# SolderingStation_Control.net
KiCad netlist of a schematic drawn in Altium Designer
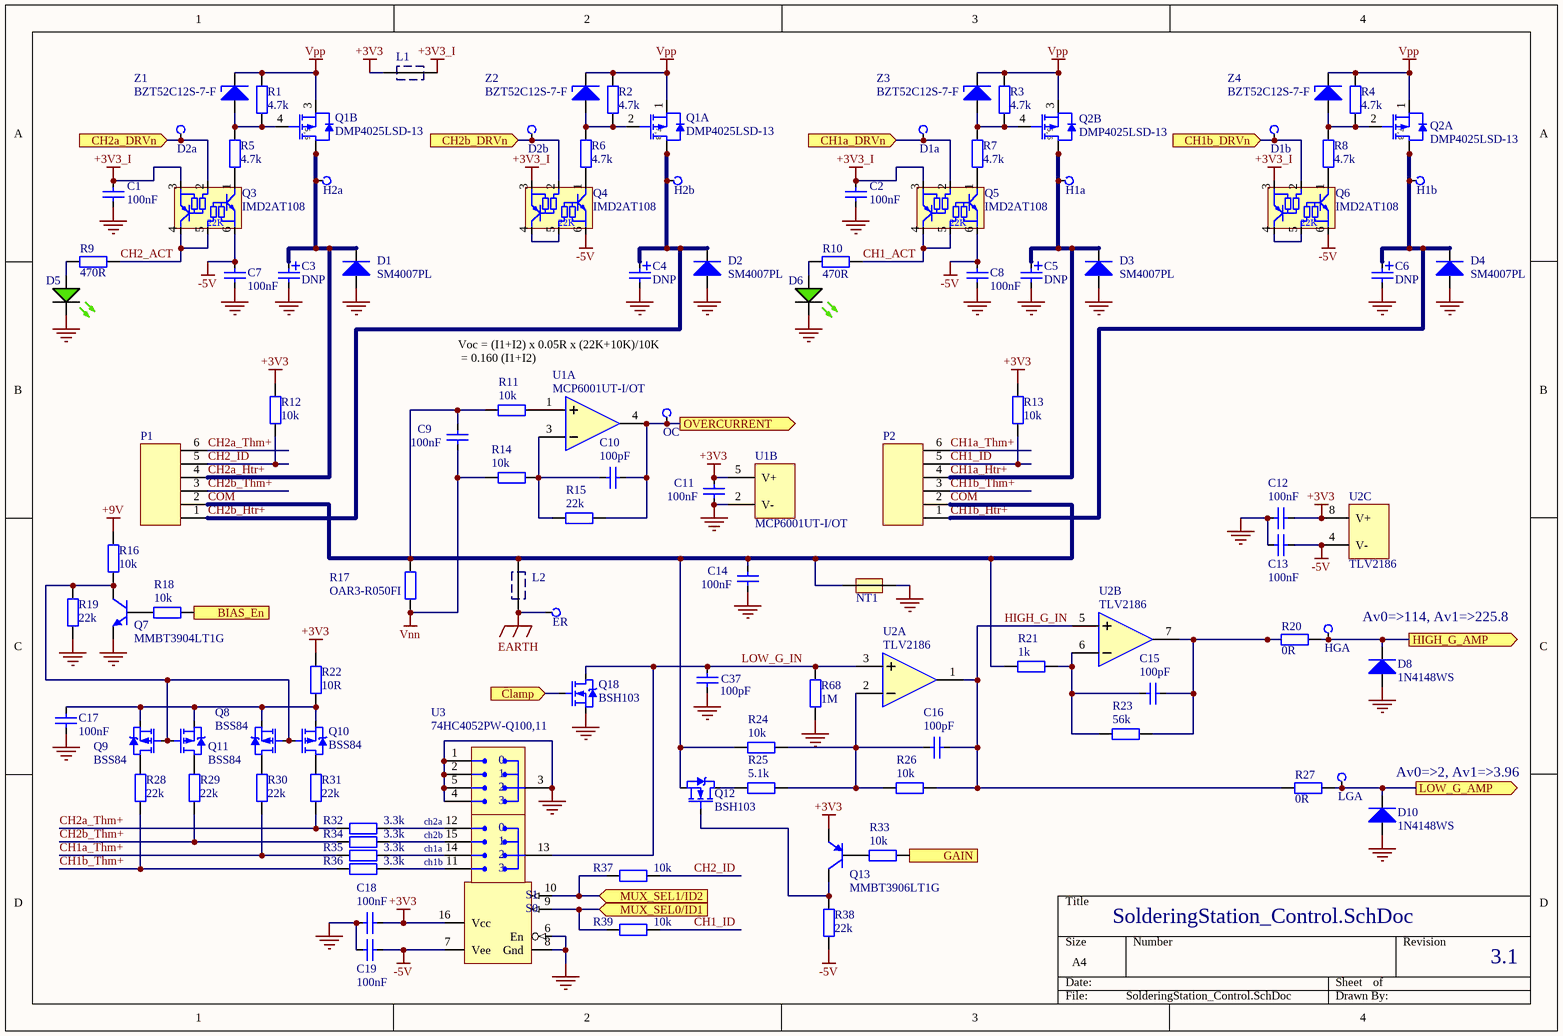
[diagram p0: SolderingStation_Control.SchDoc]

(export (version "E")
  (design (tool "Eeschema 10.0.6"))
  (components
    (comp (ref "C1")
      (value "100nF")
      (footprint "CCNP1608-0603_N")
      (description "Capacitor non-polar SMT 0603")
      (fields
        (field (name "MANUFACTURER") "Generic Components")
        (field (name "PUBLISHER") "Altium Hobart Technology Centre")
      )
      (libsource (lib "MyLibrary") (part "Cap_CCNP_0603_100nF"))
    )
    (comp (ref "C2")
      (value "100nF")
      (footprint "CCNP1608-0603_N")
      (description "Capacitor non-polar SMT 0603")
      (fields
        (field (name "MANUFACTURER") "Generic Components")
        (field (name "PUBLISHER") "Altium Hobart Technology Centre")
      )
      (libsource (lib "MyLibrary") (part "Cap_CCNP_0603_100nF"))
    )
    (comp (ref "C3")
      (value "DNP")
      (footprint "CC2012-0805")
      (description "Capacitor SMT 0805")
      (fields
        (field (name "MANUFACTURER") "Generic Components")
        (field (name "PUBLISHER") "Altium Hobart Technology Centre")
      )
      (libsource (lib "MyLibrary") (part "Cap_CC_0805"))
    )
    (comp (ref "C4")
      (value "DNP")
      (footprint "CC2012-0805")
      (description "Capacitor SMT 0805")
      (fields
        (field (name "MANUFACTURER") "Generic Components")
        (field (name "PUBLISHER") "Altium Hobart Technology Centre")
      )
      (libsource (lib "MyLibrary") (part "Cap_CC_0805"))
    )
    (comp (ref "C5")
      (value "DNP")
      (footprint "CC2012-0805")
      (description "Capacitor SMT 0805")
      (fields
        (field (name "MANUFACTURER") "Generic Components")
        (field (name "PUBLISHER") "Altium Hobart Technology Centre")
      )
      (libsource (lib "MyLibrary") (part "Cap_CC_0805"))
    )
    (comp (ref "C6")
      (value "DNP")
      (footprint "CC2012-0805")
      (description "Capacitor SMT 0805")
      (fields
        (field (name "MANUFACTURER") "Generic Components")
        (field (name "PUBLISHER") "Altium Hobart Technology Centre")
      )
      (libsource (lib "MyLibrary") (part "Cap_CC_0805"))
    )
    (comp (ref "C7")
      (value "100nF")
      (footprint "CCNP1608-0603_N")
      (description "Capacitor non-polar SMT 0603")
      (fields
        (field (name "MANUFACTURER") "Generic Components")
        (field (name "PUBLISHER") "Altium Hobart Technology Centre")
      )
      (libsource (lib "MyLibrary") (part "Cap_CCNP_0603_100nF"))
    )
    (comp (ref "C8")
      (value "100nF")
      (footprint "CCNP1608-0603_N")
      (description "Capacitor non-polar SMT 0603")
      (fields
        (field (name "MANUFACTURER") "Generic Components")
        (field (name "PUBLISHER") "Altium Hobart Technology Centre")
      )
      (libsource (lib "MyLibrary") (part "Cap_CCNP_0603_100nF"))
    )
    (comp (ref "C9")
      (value "100nF")
      (footprint "CCNP1608-0603_N")
      (description "Capacitor non-polar SMT 0603")
      (fields
        (field (name "MANUFACTURER") "Generic Components")
        (field (name "PUBLISHER") "Altium Hobart Technology Centre")
      )
      (libsource (lib "MyLibrary") (part "Cap_CCNP_0603_100nF"))
    )
    (comp (ref "C10")
      (value "100pF")
      (footprint "CCNP1608-0603_N")
      (description "Capacitor non-polar SMT 0603")
      (fields
        (field (name "MANUFACTURER") "Generic Components")
        (field (name "PUBLISHER") "Altium Hobart Technology Centre")
      )
      (libsource (lib "MyLibrary") (part "Cap_CCNP_0603_100pF"))
    )
    (comp (ref "C11")
      (value "100nF")
      (footprint "CCNP1608-0603_N")
      (description "Capacitor non-polar SMT 0603")
      (fields
        (field (name "MANUFACTURER") "Generic Components")
        (field (name "PUBLISHER") "Altium Hobart Technology Centre")
      )
      (libsource (lib "MyLibrary") (part "Cap_CCNP_0603_100nF"))
    )
    (comp (ref "C12")
      (value "100nF")
      (footprint "CCNP1608-0603_N")
      (description "Capacitor non-polar SMT 0603")
      (fields
        (field (name "MANUFACTURER") "Generic Components")
        (field (name "PUBLISHER") "Altium Hobart Technology Centre")
      )
      (libsource (lib "MyLibrary") (part "Cap_CCNP_0603_100nF"))
    )
    (comp (ref "C13")
      (value "100nF")
      (footprint "CCNP1608-0603_N")
      (description "Capacitor non-polar SMT 0603")
      (fields
        (field (name "MANUFACTURER") "Generic Components")
        (field (name "PUBLISHER") "Altium Hobart Technology Centre")
      )
      (libsource (lib "MyLibrary") (part "Cap_CCNP_0603_100nF"))
    )
    (comp (ref "C14")
      (value "100nF")
      (footprint "CCNP1608-0603_N")
      (description "Capacitor non-polar SMT 0603")
      (fields
        (field (name "MANUFACTURER") "Generic Components")
        (field (name "PUBLISHER") "Altium Hobart Technology Centre")
      )
      (libsource (lib "MyLibrary") (part "Cap_CCNP_0603_100nF"))
    )
    (comp (ref "C15")
      (value "100pF")
      (footprint "CCNP1608-0603_N")
      (description "Capacitor non-polar SMT 0603")
      (fields
        (field (name "MANUFACTURER") "Generic Components")
        (field (name "PUBLISHER") "Altium Hobart Technology Centre")
      )
      (libsource (lib "MyLibrary") (part "Cap_CCNP_0603_100pF"))
    )
    (comp (ref "C16")
      (value "100pF")
      (footprint "CCNP1608-0603_N")
      (description "Capacitor non-polar SMT 0603")
      (fields
        (field (name "MANUFACTURER") "Generic Components")
        (field (name "PUBLISHER") "Altium Hobart Technology Centre")
      )
      (libsource (lib "MyLibrary") (part "Cap_CCNP_0603_100pF"))
    )
    (comp (ref "C17")
      (value "100nF")
      (footprint "CCNP1608-0603_N")
      (description "Capacitor non-polar SMT 0603")
      (fields
        (field (name "MANUFACTURER") "Generic Components")
        (field (name "PUBLISHER") "Altium Hobart Technology Centre")
      )
      (libsource (lib "MyLibrary") (part "Cap_CCNP_0603_100nF"))
    )
    (comp (ref "C18")
      (value "100nF")
      (footprint "CCNP1608-0603_N")
      (description "Capacitor non-polar SMT 0603")
      (fields
        (field (name "MANUFACTURER") "Generic Components")
        (field (name "PUBLISHER") "Altium Hobart Technology Centre")
      )
      (libsource (lib "MyLibrary") (part "Cap_CCNP_0603_100nF"))
    )
    (comp (ref "C19")
      (value "100nF")
      (footprint "CCNP1608-0603_N")
      (description "Capacitor non-polar SMT 0603")
      (fields
        (field (name "MANUFACTURER") "Generic Components")
        (field (name "PUBLISHER") "Altium Hobart Technology Centre")
      )
      (libsource (lib "MyLibrary") (part "Cap_CCNP_0603_100nF"))
    )
    (comp (ref "C37")
      (value "100pF")
      (footprint "CCNP1608-0603_N")
      (description "Capacitor non-polar SMT 0603")
      (fields
        (field (name "MANUFACTURER") "Generic Components")
        (field (name "PUBLISHER") "Altium Hobart Technology Centre")
      )
      (libsource (lib "MyLibrary") (part "Cap_CCNP_0603_100pF"))
    )
    (comp (ref "D1")
      (value "SM4007PL")
      (footprint "SOD-123FL")
      (description "Diodes - General Purpose, 1kV 1A 1.1V 1A SOD-123FL")
      (libsource (lib "MyLibrary") (part "SM4007PL"))
    )
    (comp (ref "D1a")
      (value "Drive1")
      (footprint "PCBPIN - 0.9mm")
      (description "Test Point")
      (libsource (lib "") (part "TP_1"))
    )
    (comp (ref "D1b")
      (value "Drive2")
      (footprint "PCBPIN - 0.9mm")
      (description "Test Point")
      (libsource (lib "") (part "TP_1"))
    )
    (comp (ref "D2")
      (value "SM4007PL")
      (footprint "SOD-123FL")
      (description "Diodes - General Purpose, 1kV 1A 1.1V 1A SOD-123FL")
      (libsource (lib "MyLibrary") (part "SM4007PL"))
    )
    (comp (ref "D2a")
      (value "Drive2")
      (footprint "PCBPIN - 0.9mm")
      (description "Test Point")
      (libsource (lib "") (part "TP_1"))
    )
    (comp (ref "D2b")
      (value "Drive2")
      (footprint "PCBPIN - 0.9mm")
      (description "Test Point")
      (libsource (lib "") (part "TP_1"))
    )
    (comp (ref "D3")
      (value "SM4007PL")
      (footprint "SOD-123FL")
      (description "Diodes - General Purpose, 1kV 1A 1.1V 1A SOD-123FL")
      (libsource (lib "MyLibrary") (part "SM4007PL"))
    )
    (comp (ref "D4")
      (value "SM4007PL")
      (footprint "SOD-123FL")
      (description "Diodes - General Purpose, 1kV 1A 1.1V 1A SOD-123FL")
      (libsource (lib "MyLibrary") (part "SM4007PL"))
    )
    (comp (ref "D5")
      (value "LED")
      (footprint "LED3MM-GREEN - 10mm Proud")
      (description "3mm Green LED")
      (fields (field (name "MANUFACTURER") "Generic Components") (field (name "PUBLISHER") "Altium Limited"))
      (libsource (lib "MySchLib") (part "LED_3MM_GREEN"))
    )
    (comp (ref "D6")
      (value "LED")
      (footprint "LED3MM-GREEN - 10mm Proud")
      (description "3mm Green LED")
      (fields (field (name "MANUFACTURER") "Generic Components") (field (name "PUBLISHER") "Altium Limited"))
      (libsource (lib "MySchLib") (part "LED_3MM_GREEN"))
    )
    (comp (ref "D8")
      (value "1N4148WS")
      (footprint "SOD-323")
      (description "Switching Diode 100V 150mA 1.25V@150mA 4ns SOD-323")
      (libsource (lib "MyLibrary") (part "1N4148WS"))
    )
    (comp (ref "D10")
      (value "1N4148WS")
      (footprint "SOD-323")
      (description "Switching Diode 100V 150mA 1.25V@150mA 4ns SOD-323")
      (libsource (lib "MyLibrary") (part "1N4148WS"))
    )
    (comp (ref "ER")
      (value "Gnd")
      (footprint "PCBPIN - 0.9mm")
      (description "Test Point")
      (libsource (lib "MySchLib") (part "TP"))
    )
    (comp (ref "H1a")
      (value "Heater1")
      (footprint "PCBPIN - 0.9mm")
      (description "Test Point")
      (libsource (lib "MySchLib") (part "TP"))
    )
    (comp (ref "H1b")
      (value "Heater2")
      (footprint "PCBPIN - 0.9mm")
      (description "Test Point")
      (libsource (lib "MySchLib") (part "TP"))
    )
    (comp (ref "H2a")
      (value "Heater2")
      (footprint "PCBPIN - 0.9mm")
      (description "Test Point")
      (libsource (lib "MySchLib") (part "TP"))
    )
    (comp (ref "H2b")
      (value "Heater2")
      (footprint "PCBPIN - 0.9mm")
      (description "Test Point")
      (libsource (lib "MySchLib") (part "TP"))
    )
    (comp (ref "HGA")
      (value "TC1")
      (footprint "PCBPIN - 0.9mm")
      (description "Test Point")
      (libsource (lib "") (part "TP_1"))
    )
    (comp (ref "L1")
      (value "Ferrite Bead")
      (footprint "FB2012-0805")
      (description "Ferrite Bead SMT 0805, TDK MPZ2012S102AT, 0.15OHM, 1.5A")
      (libsource (lib "MySchLib") (part "Ferrite Bead 0805"))
    )
    (comp (ref "L2")
      (value "Ferrite Bead")
      (footprint "FB2012-0805")
      (description "Ferrite Bead SMT 0805, TDK MPZ2012S102AT, 0.15OHM, 1.5A")
      (libsource (lib "MySchLib") (part "Ferrite Bead 0805"))
    )
    (comp (ref "LGA")
      (value "NTC1")
      (footprint "PCBPIN - 0.9mm")
      (description "Test Point")
      (libsource (lib "") (part "TP_1"))
    )
    (comp (ref "NT1")
      (value "NetTieVia")
      (footprint "NetTieVia")
      (libsource (lib "MyLibrary") (part "NetTieVia"))
    )
    (comp (ref "OC")
      (value "Overcurrent")
      (footprint "PCBPIN - 0.9mm")
      (description "Test Point")
      (libsource (lib "") (part "TP_1"))
    )
    (comp (ref "P1")
      (value "MOLEX-43045-0612")
      (footprint "MOLEX-43045-0612")
      (description "Wire-To-Board Connector, With Polarizing Peg, 3 mm, 6 Contacts, Header, Micro-Fit 3.0 43045 Series")
      (libsource (lib "MySchLib") (part "MOLEX-43045-0612"))
    )
    (comp (ref "P2")
      (value "MOLEX-43045-0612")
      (footprint "MOLEX-43045-0612")
      (description "Wire-To-Board Connector, With Polarizing Peg, 3 mm, 6 Contacts, Header, Micro-Fit 3.0 43045 Series")
      (libsource (lib "MySchLib") (part "MOLEX-43045-0612"))
    )
    (comp (ref "Q1")
      (value "DMP4025LSD-13")
      (footprint "SO-8_M")
      (description "P-Channel dual MOSFET, 40 V, 7.6 A, 0.018 ohm, SOIC, Surface Mount")
      (libsource (lib "MyLibrary") (part "DMP4025LSD-13"))
    )
    (comp (ref "Q2")
      (value "DMP4025LSD-13")
      (footprint "SO-8_M")
      (description "P-Channel dual MOSFET, 40 V, 7.6 A, 0.018 ohm, SOIC, Surface Mount")
      (libsource (lib "MyLibrary") (part "DMP4025LSD-13"))
    )
    (comp (ref "Q3")
      (value "IMD2AT108")
      (footprint "SOT457_N - MIRROR")
      (description "Pre-Biased NPN and PNP pair, 50 V, 100 mA, 22 kohm, 22 kohm")
      (libsource (lib "MySchLib") (part "IMD2AT108"))
    )
    (comp (ref "Q4")
      (value "IMD2AT108")
      (footprint "SOT457_N - MIRROR")
      (description "Pre-Biased NPN and PNP pair, 50 V, 100 mA, 22 kohm, 22 kohm")
      (libsource (lib "MySchLib") (part "IMD2AT108"))
    )
    (comp (ref "Q5")
      (value "IMD2AT108")
      (footprint "SOT457_N - MIRROR")
      (description "Pre-Biased NPN and PNP pair, 50 V, 100 mA, 22 kohm, 22 kohm")
      (libsource (lib "MySchLib") (part "IMD2AT108"))
    )
    (comp (ref "Q6")
      (value "IMD2AT108")
      (footprint "SOT457_N - MIRROR")
      (description "Pre-Biased NPN and PNP pair, 50 V, 100 mA, 22 kohm, 22 kohm")
      (libsource (lib "MySchLib") (part "IMD2AT108"))
    )
    (comp (ref "Q7")
      (value "MMBT3904LT1G")
      (footprint "SOT23_N")
      (description "General Purpose Transistor, NPN Silicon, 3-Pin SOT-23, Pb-Free, Tape and Reel")
      (fields (field (name "MANUFACTURER") "On Semiconductor"))
      (libsource (lib "MyLibrary") (part "MMBT3904LT1G"))
    )
    (comp (ref "Q8")
      (value "BSS84")
      (footprint "SOT23_M")
      (description "P-Channel Enhancement Mode FET -0.13 A, -50 V,  RDS(ON) = 10R at VGS = -5 V")
      (libsource (lib "MySchLib") (part "BSS84"))
    )
    (comp (ref "Q9")
      (value "BSS84")
      (footprint "SOT23_M")
      (description "P-Channel Enhancement Mode FET -0.13 A, -50 V,  RDS(ON) = 10R at VGS = -5 V")
      (libsource (lib "MySchLib") (part "BSS84"))
    )
    (comp (ref "Q10")
      (value "BSS84")
      (footprint "SOT23_M")
      (description "P-Channel Enhancement Mode FET -0.13 A, -50 V,  RDS(ON) = 10R at VGS = -5 V")
      (libsource (lib "MySchLib") (part "BSS84"))
    )
    (comp (ref "Q11")
      (value "BSS84")
      (footprint "SOT23_M")
      (description "P-Channel Enhancement Mode FET -0.13 A, -50 V,  RDS(ON) = 10R at VGS = -5 V")
      (libsource (lib "MySchLib") (part "BSS84"))
    )
    (comp (ref "Q12")
      (value "BSH103")
      (footprint "SOT23_N")
      (description "N-channel enhancement mode FET, , 30 V, 850 mA, 0.4 ohm, SOT23")
      (libsource (lib "MyLibrary") (part "BSH103"))
    )
    (comp (ref "Q13")
      (value "MMBT3906LT1G")
      (footprint "SOT23_N")
      (description "General Purpose Transistor, PNP Silicon, 3-Pin SOT-23, Pb-Free, Tape and Reel")
      (fields (field (name "MANUFACTURER") "On Semiconductor"))
      (libsource (lib "MyLibrary") (part "MMBT3906LT1G"))
    )
    (comp (ref "Q18")
      (value "BSH103")
      (footprint "SOT23_N")
      (description "N-channel enhancement mode FET, , 30 V, 850 mA, 0.4 ohm, SOT23")
      (libsource (lib "MyLibrary") (part "BSH103"))
    )
    (comp (ref "R1")
      (value "4.7k")
      (footprint "CR1608-0603_N")
      (description "Resistor SMT 0603")
      (fields
        (field (name "MANUFACTURER") "Generic Components")
        (field (name "PUBLISHER") "Altium Hobart Technology Centre")
      )
      (libsource (lib "MyLibrary") (part "Res_CR0603_4k7"))
    )
    (comp (ref "R2")
      (value "4.7k")
      (footprint "CR1608-0603_N")
      (description "Resistor SMT 0603")
      (fields
        (field (name "MANUFACTURER") "Generic Components")
        (field (name "PUBLISHER") "Altium Hobart Technology Centre")
      )
      (libsource (lib "MyLibrary") (part "Res_CR0603_4k7"))
    )
    (comp (ref "R3")
      (value "4.7k")
      (footprint "CR1608-0603_N")
      (description "Resistor SMT 0603")
      (fields
        (field (name "MANUFACTURER") "Generic Components")
        (field (name "PUBLISHER") "Altium Hobart Technology Centre")
      )
      (libsource (lib "MyLibrary") (part "Res_CR0603_4k7"))
    )
    (comp (ref "R4")
      (value "4.7k")
      (footprint "CR1608-0603_N")
      (description "Resistor SMT 0603")
      (fields
        (field (name "MANUFACTURER") "Generic Components")
        (field (name "PUBLISHER") "Altium Hobart Technology Centre")
      )
      (libsource (lib "MyLibrary") (part "Res_CR0603_4k7"))
    )
    (comp (ref "R5")
      (value "4.7k")
      (footprint "CR1608-0603_N")
      (description "Resistor SMT 0603")
      (fields
        (field (name "MANUFACTURER") "Generic Components")
        (field (name "PUBLISHER") "Altium Hobart Technology Centre")
      )
      (libsource (lib "MyLibrary") (part "Res_CR0603_4k7"))
    )
    (comp (ref "R6")
      (value "4.7k")
      (footprint "CR1608-0603_N")
      (description "Resistor SMT 0603")
      (fields
        (field (name "MANUFACTURER") "Generic Components")
        (field (name "PUBLISHER") "Altium Hobart Technology Centre")
      )
      (libsource (lib "MyLibrary") (part "Res_CR0603_4k7"))
    )
    (comp (ref "R7")
      (value "4.7k")
      (footprint "CR1608-0603_N")
      (description "Resistor SMT 0603")
      (fields
        (field (name "MANUFACTURER") "Generic Components")
        (field (name "PUBLISHER") "Altium Hobart Technology Centre")
      )
      (libsource (lib "MyLibrary") (part "Res_CR0603_4k7"))
    )
    (comp (ref "R8")
      (value "4.7k")
      (footprint "CR1608-0603_N")
      (description "Resistor SMT 0603")
      (fields
        (field (name "MANUFACTURER") "Generic Components")
        (field (name "PUBLISHER") "Altium Hobart Technology Centre")
      )
      (libsource (lib "MyLibrary") (part "Res_CR0603_4k7"))
    )
    (comp (ref "R9")
      (value "470R")
      (footprint "CR1608-0603_N")
      (description "Resistor SMT 0603")
      (fields
        (field (name "MANUFACTURER") "Generic Components")
        (field (name "PUBLISHER") "Altium Hobart Technology Centre")
      )
      (libsource (lib "MyLibrary") (part "Res_CR0603_470R"))
    )
    (comp (ref "R10")
      (value "470R")
      (footprint "CR1608-0603_N")
      (description "Resistor SMT 0603")
      (fields
        (field (name "MANUFACTURER") "Generic Components")
        (field (name "PUBLISHER") "Altium Hobart Technology Centre")
      )
      (libsource (lib "MyLibrary") (part "Res_CR0603_470R"))
    )
    (comp (ref "R11")
      (value "10k")
      (footprint "CR1608-0603_N")
      (description "Resistor SMT 0603")
      (fields
        (field (name "MANUFACTURER") "Generic Components")
        (field (name "PUBLISHER") "Altium Hobart Technology Centre")
      )
      (libsource (lib "") (part "Res_CR0603_10k_1"))
    )
    (comp (ref "R12")
      (value "10k")
      (footprint "CR1608-0603_N")
      (description "Resistor SMT 0603")
      (fields
        (field (name "MANUFACTURER") "Generic Components")
        (field (name "PUBLISHER") "Altium Hobart Technology Centre")
      )
      (libsource (lib "MyLibrary") (part "Res_CR0603_10k"))
    )
    (comp (ref "R13")
      (value "10k")
      (footprint "CR1608-0603_N")
      (description "Resistor SMT 0603")
      (fields
        (field (name "MANUFACTURER") "Generic Components")
        (field (name "PUBLISHER") "Altium Hobart Technology Centre")
      )
      (libsource (lib "MyLibrary") (part "Res_CR0603_10k"))
    )
    (comp (ref "R14")
      (value "10k")
      (footprint "CR1608-0603_N")
      (description "Resistor SMT 0603")
      (fields
        (field (name "MANUFACTURER") "Generic Components")
        (field (name "PUBLISHER") "Altium Hobart Technology Centre")
      )
      (libsource (lib "") (part "Res_CR0603_10k_1"))
    )
    (comp (ref "R15")
      (value "22k")
      (footprint "CR1608-0603_N")
      (description "Resistor SMT 0603")
      (fields
        (field (name "MANUFACTURER") "Generic Components")
        (field (name "PUBLISHER") "Altium Hobart Technology Centre")
      )
      (libsource (lib "") (part "Res_CR0603_22k_1"))
    )
    (comp (ref "R16")
      (value "10k")
      (footprint "CR1608-0603_N")
      (description "Resistor SMT 0603")
      (fields
        (field (name "MANUFACTURER") "Generic Components")
        (field (name "PUBLISHER") "Altium Hobart Technology Centre")
      )
      (libsource (lib "") (part "Res_CR0603_10k_3"))
    )
    (comp (ref "R17")
      (value "OAR3-R050FI")
      (footprint "OAR3-R050FI")
      (description "Current Sense Resistor, 0.05 ohm, OAR Series, 3 W, Metal Strip, Radial Leaded, 1%")
      (libsource (lib "MySchLib") (part "OAR3-R050FI"))
    )
    (comp (ref "R18")
      (value "10k")
      (footprint "CR1608-0603_N")
      (description "Resistor SMT 0603")
      (fields
        (field (name "MANUFACTURER") "Generic Components")
        (field (name "PUBLISHER") "Altium Hobart Technology Centre")
      )
      (libsource (lib "") (part "Res_CR0603_10k_2"))
    )
    (comp (ref "R19")
      (value "22k")
      (footprint "CR1608-0603_N")
      (description "Resistor SMT 0603")
      (fields
        (field (name "MANUFACTURER") "Generic Components")
        (field (name "PUBLISHER") "Altium Hobart Technology Centre")
      )
      (libsource (lib "MyLibrary") (part "Res_CR0603_22k"))
    )
    (comp (ref "R20")
      (value "0R")
      (footprint "CR1608-0603_N")
      (description "Resistor SMT 0603")
      (fields
        (field (name "MANUFACTURER") "Generic Components")
        (field (name "PUBLISHER") "Altium Hobart Technology Centre")
      )
      (libsource (lib "MyLibrary") (part "Res_CR0603_0R"))
    )
    (comp (ref "R21")
      (value "1k")
      (footprint "CR1608-0603_N")
      (description "Resistor SMT 0603")
      (fields
        (field (name "MANUFACTURER") "Generic Components")
        (field (name "PUBLISHER") "Altium Hobart Technology Centre")
      )
      (libsource (lib "MyLibrary") (part "Res_CR0603_1k"))
    )
    (comp (ref "R22")
      (value "10R")
      (footprint "CR1608-0603_N")
      (description "Resistor SMT 0603")
      (fields
        (field (name "MANUFACTURER") "Generic Components")
        (field (name "PUBLISHER") "Altium Hobart Technology Centre")
      )
      (libsource (lib "MyLibrary") (part "Res_CR0603_10R"))
    )
    (comp (ref "R23")
      (value "56k")
      (footprint "CR1608-0603_N")
      (description "Resistor SMT 0603")
      (fields
        (field (name "MANUFACTURER") "Generic Components")
        (field (name "PUBLISHER") "Altium Hobart Technology Centre")
      )
      (libsource (lib "MyLibrary") (part "Res_CR0603_56k"))
    )
    (comp (ref "R24")
      (value "10k")
      (footprint "CR1608-0603_N")
      (description "Resistor SMT 0603")
      (fields
        (field (name "MANUFACTURER") "Generic Components")
        (field (name "PUBLISHER") "Altium Hobart Technology Centre")
      )
      (libsource (lib "") (part "Res_CR0603_10k_2"))
    )
    (comp (ref "R25")
      (value "5.1k")
      (footprint "CR1608-0603_N")
      (description "Resistor SMT 0603")
      (fields
        (field (name "MANUFACTURER") "Generic Components")
        (field (name "PUBLISHER") "Altium Hobart Technology Centre")
      )
      (libsource (lib "MyLibrary") (part "Res_CR0603_5k1"))
    )
    (comp (ref "R26")
      (value "10k")
      (footprint "CR1608-0603_N")
      (description "Resistor SMT 0603")
      (fields
        (field (name "MANUFACTURER") "Generic Components")
        (field (name "PUBLISHER") "Altium Hobart Technology Centre")
      )
      (libsource (lib "") (part "Res_CR0603_10k_2"))
    )
    (comp (ref "R27")
      (value "0R")
      (footprint "CR1608-0603_N")
      (description "Resistor SMT 0603")
      (fields
        (field (name "MANUFACTURER") "Generic Components")
        (field (name "PUBLISHER") "Altium Hobart Technology Centre")
      )
      (libsource (lib "MyLibrary") (part "Res_CR0603_0R"))
    )
    (comp (ref "R28")
      (value "22k")
      (footprint "CR1608-0603_N")
      (description "Resistor SMT 0603")
      (fields
        (field (name "MANUFACTURER") "Generic Components")
        (field (name "PUBLISHER") "Altium Hobart Technology Centre")
      )
      (libsource (lib "") (part "Res_CR0603_22k_1"))
    )
    (comp (ref "R29")
      (value "22k")
      (footprint "CR1608-0603_N")
      (description "Resistor SMT 0603")
      (fields
        (field (name "MANUFACTURER") "Generic Components")
        (field (name "PUBLISHER") "Altium Hobart Technology Centre")
      )
      (libsource (lib "") (part "Res_CR0603_22k_1"))
    )
    (comp (ref "R30")
      (value "22k")
      (footprint "CR1608-0603_N")
      (description "Resistor SMT 0603")
      (fields
        (field (name "MANUFACTURER") "Generic Components")
        (field (name "PUBLISHER") "Altium Hobart Technology Centre")
      )
      (libsource (lib "MyLibrary") (part "Res_CR0603_22k"))
    )
    (comp (ref "R31")
      (value "22k")
      (footprint "CR1608-0603_N")
      (description "Resistor SMT 0603")
      (fields
        (field (name "MANUFACTURER") "Generic Components")
        (field (name "PUBLISHER") "Altium Hobart Technology Centre")
      )
      (libsource (lib "MyLibrary") (part "Res_CR0603_22k"))
    )
    (comp (ref "R32")
      (value "3.3k")
      (footprint "CR1608-0603_N")
      (description "Resistor SMT 0603")
      (fields
        (field (name "MANUFACTURER") "Generic Components")
        (field (name "PUBLISHER") "Altium Hobart Technology Centre")
      )
      (libsource (lib "MyLibrary") (part "Res_CR0603_3k3"))
    )
    (comp (ref "R33")
      (value "10k")
      (footprint "CR1608-0603_N")
      (description "Resistor SMT 0603")
      (fields
        (field (name "MANUFACTURER") "Generic Components")
        (field (name "PUBLISHER") "Altium Hobart Technology Centre")
      )
      (libsource (lib "") (part "Res_CR0603_10k_2"))
    )
    (comp (ref "R34")
      (value "3.3k")
      (footprint "CR1608-0603_N")
      (description "Resistor SMT 0603")
      (fields
        (field (name "MANUFACTURER") "Generic Components")
        (field (name "PUBLISHER") "Altium Hobart Technology Centre")
      )
      (libsource (lib "MyLibrary") (part "Res_CR0603_3k3"))
    )
    (comp (ref "R35")
      (value "3.3k")
      (footprint "CR1608-0603_N")
      (description "Resistor SMT 0603")
      (fields
        (field (name "MANUFACTURER") "Generic Components")
        (field (name "PUBLISHER") "Altium Hobart Technology Centre")
      )
      (libsource (lib "MyLibrary") (part "Res_CR0603_3k3"))
    )
    (comp (ref "R36")
      (value "3.3k")
      (footprint "CR1608-0603_N")
      (description "Resistor SMT 0603")
      (fields
        (field (name "MANUFACTURER") "Generic Components")
        (field (name "PUBLISHER") "Altium Hobart Technology Centre")
      )
      (libsource (lib "MyLibrary") (part "Res_CR0603_3k3"))
    )
    (comp (ref "R37")
      (value "10k")
      (footprint "CR1608-0603_N")
      (description "Resistor SMT 0603")
      (fields
        (field (name "MANUFACTURER") "Generic Components")
        (field (name "PUBLISHER") "Altium Hobart Technology Centre")
      )
      (libsource (lib "") (part "Res_CR0603_10k_3"))
    )
    (comp (ref "R38")
      (value "22k")
      (footprint "CR1608-0603_N")
      (description "Resistor SMT 0603")
      (fields
        (field (name "MANUFACTURER") "Generic Components")
        (field (name "PUBLISHER") "Altium Hobart Technology Centre")
      )
      (libsource (lib "MyLibrary") (part "Res_CR0603_22k"))
    )
    (comp (ref "R39")
      (value "10k")
      (footprint "CR1608-0603_N")
      (description "Resistor SMT 0603")
      (fields
        (field (name "MANUFACTURER") "Generic Components")
        (field (name "PUBLISHER") "Altium Hobart Technology Centre")
      )
      (libsource (lib "") (part "Res_CR0603_10k_3"))
    )
    (comp (ref "R68")
      (value "1M")
      (footprint "CR1608-0603_N")
      (description "Resistor SMT 0603")
      (fields
        (field (name "MANUFACTURER") "Generic Components")
        (field (name "PUBLISHER") "Altium Hobart Technology Centre")
      )
      (libsource (lib "MyLibrary") (part "Res_CR0603_1M"))
    )
    (comp (ref "U1")
      (value "MCP6001UT-I/OT")
      (footprint "SOT23-5_M")
      (description "Op-Amp, Single supply R-R in/out")
      (libsource (lib "") (part "MCP6001UT-I/OT_1"))
    )
    (comp (ref "U2")
      (value "TLV2186")
      (footprint "SOIC127P600-8M")
      (description "Dual Precision,Rail-to-Rail Input and Output, 4.5-24V, Zero-Drift OperationalAmplifier")
      (libsource (lib "MySchLib") (part "TLV2186"))
    )
    (comp (ref "U3")
      (value "74HC4052PW-Q100,11")
      (footprint "TSSOP16_M")
      (description "Analog Multiplexer / Demultiplexer, 4:1, 2 Circuits, 225 ohm, 2V to 10V, TSSOP-16")
      (libsource (lib "MySchLib") (part "74HC4052PW-Q100,11"))
    )
    (comp (ref "Z1")
      (value "BZT52C12S-7-F")
      (footprint "SOD-323")
      (description "Surface Mount Zener Diode, 12-13 V, -65 to 150 degC, SOD-123")
      (libsource (lib "MySchLib") (part "BZT52C12S-7-F"))
    )
    (comp (ref "Z2")
      (value "BZT52C12S-7-F")
      (footprint "SOD-323")
      (description "Surface Mount Zener Diode, 12-13 V, -65 to 150 degC, SOD-123")
      (libsource (lib "MySchLib") (part "BZT52C12S-7-F"))
    )
    (comp (ref "Z3")
      (value "BZT52C12S-7-F")
      (footprint "SOD-323")
      (description "Surface Mount Zener Diode, 12-13 V, -65 to 150 degC, SOD-123")
      (libsource (lib "MySchLib") (part "BZT52C12S-7-F"))
    )
    (comp (ref "Z4")
      (value "BZT52C12S-7-F")
      (footprint "SOD-323")
      (description "Surface Mount Zener Diode, 12-13 V, -65 to 150 degC, SOD-123")
      (libsource (lib "MySchLib") (part "BZT52C12S-7-F"))
    )
  )
  (nets
    (net (code "1") (name "+3V3") (class "Default")
      (node (ref "C11") (pin "1") (pinfunction "1_1") (pintype "passive"))
      (node (ref "C12") (pin "1") (pinfunction "1_1") (pintype "passive"))
      (node (ref "C18") (pin "1") (pinfunction "1_1") (pintype "passive"))
      (node (ref "L1") (pin "1") (pinfunction "1_1") (pintype "passive"))
      (node (ref "Q13") (pin "2") (pinfunction "E_2") (pintype "passive"))
      (node (ref "R12") (pin "2") (pinfunction "2_2") (pintype "passive"))
      (node (ref "R13") (pin "2") (pinfunction "2_2") (pintype "passive"))
      (node (ref "R22") (pin "1") (pinfunction "1_1") (pintype "passive"))
      (node (ref "U1") (pin "5") (pinfunction "V+_5") (pintype "power_in"))
      (node (ref "U2") (pin "8") (pinfunction "V+_8") (pintype "power_in"))
      (node (ref "U3") (pin "16") (pinfunction "Vcc_16") (pintype "power_in"))
    )
    (net (code "2") (name "+3V3_I") (class "Default")
      (node (ref "C1") (pin "1") (pinfunction "1_1") (pintype "passive"))
      (node (ref "C2") (pin "1") (pinfunction "1_1") (pintype "passive"))
      (node (ref "L1") (pin "2") (pinfunction "2_2") (pintype "passive"))
      (node (ref "Q3") (pin "3") (pinfunction "E2_3") (pintype "passive"))
      (node (ref "Q4") (pin "3") (pinfunction "E2_3") (pintype "passive"))
      (node (ref "Q5") (pin "3") (pinfunction "E2_3") (pintype "passive"))
      (node (ref "Q6") (pin "3") (pinfunction "E2_3") (pintype "passive"))
    )
    (net (code "3") (name "+9V") (class "Default")
      (node (ref "R16") (pin "1") (pinfunction "1_1") (pintype "passive"))
    )
    (net (code "4") (name "-5V") (class "Default")
      (node (ref "C13") (pin "1") (pinfunction "1_1") (pintype "passive"))
      (node (ref "C19") (pin "1") (pinfunction "1_1") (pintype "passive"))
      (node (ref "C7") (pin "1") (pinfunction "1_1") (pintype "passive"))
      (node (ref "C8") (pin "1") (pinfunction "1_1") (pintype "passive"))
      (node (ref "Q3") (pin "6") (pinfunction "E1_6") (pintype "passive"))
      (node (ref "Q4") (pin "6") (pinfunction "E1_6") (pintype "passive"))
      (node (ref "Q5") (pin "6") (pinfunction "E1_6") (pintype "passive"))
      (node (ref "Q6") (pin "6") (pinfunction "E1_6") (pintype "passive"))
      (node (ref "R38") (pin "1") (pinfunction "1_1") (pintype "passive"))
      (node (ref "U2") (pin "4") (pinfunction "V-_4") (pintype "power_in"))
      (node (ref "U3") (pin "7") (pinfunction "Vee_7") (pintype "power_in"))
    )
    (net (code "5") (name "/BIAS_En") (class "Default")
      (node (ref "R18") (pin "2") (pinfunction "2_2") (pintype "passive"))
    )
    (net (code "6") (name "/CH1_ACT") (class "Default")
      (node (ref "Q5") (pin "4") (pinfunction "C2_4") (pintype "passive"))
      (node (ref "Q5") (pin "5") (pinfunction "B1_5") (pintype "passive"))
      (node (ref "R10") (pin "2") (pinfunction "2_2") (pintype "passive"))
    )
    (net (code "7") (name "/CH1_ID") (class "Default")
      (node (ref "P2") (pin "5") (pinfunction "5_5") (pintype "passive"))
      (node (ref "R13") (pin "1") (pinfunction "1_1") (pintype "passive"))
      (node (ref "R39") (pin "1") (pinfunction "1_1") (pintype "passive"))
    )
    (net (code "8") (name "/CH1a_DRVn") (class "Default")
      (node (ref "D1a") (pin "1") (pinfunction "TP_1") (pintype "passive"))
      (node (ref "Q5") (pin "2") (pinfunction "B2_2") (pintype "passive"))
    )
    (net (code "9") (name "/CH1a_Htr+") (class "Default")
      (node (ref "C5") (pin "1") (pinfunction "1_1") (pintype "passive"))
      (node (ref "D3") (pin "K") (pinfunction "K_K") (pintype "passive"))
      (node (ref "H1a") (pin "1") (pinfunction "TP_1") (pintype "passive"))
      (node (ref "P2") (pin "4") (pinfunction "4_4") (pintype "passive"))
      (node (ref "Q2") (pin "5") (pinfunction "D2_5") (pintype "passive"))
      (node (ref "Q2") (pin "6") (pinfunction "D2_6") (pintype "passive"))
    )
    (net (code "10") (name "/CH1a_Thm+") (class "Default")
      (node (ref "P2") (pin "6") (pinfunction "6_6") (pintype "passive"))
      (node (ref "R30") (pin "1") (pinfunction "1_1") (pintype "passive"))
      (node (ref "R35") (pin "2") (pinfunction "2_2") (pintype "passive"))
    )
    (net (code "11") (name "/CH1b_DRVn") (class "Default")
      (node (ref "D1b") (pin "1") (pinfunction "TP_1") (pintype "passive"))
      (node (ref "Q6") (pin "2") (pinfunction "B2_2") (pintype "passive"))
    )
    (net (code "12") (name "/CH1b_Htr+") (class "Default")
      (node (ref "C6") (pin "1") (pinfunction "1_1") (pintype "passive"))
      (node (ref "D4") (pin "K") (pinfunction "K_K") (pintype "passive"))
      (node (ref "H1b") (pin "1") (pinfunction "TP_1") (pintype "passive"))
      (node (ref "P2") (pin "1") (pinfunction "1_1") (pintype "passive"))
      (node (ref "Q2") (pin "7") (pinfunction "D1_7") (pintype "passive"))
      (node (ref "Q2") (pin "8") (pinfunction "D1_8") (pintype "passive"))
    )
    (net (code "13") (name "/CH1b_Thm+") (class "Default")
      (node (ref "P2") (pin "3") (pinfunction "3_3") (pintype "passive"))
      (node (ref "R28") (pin "1") (pinfunction "1_1") (pintype "passive"))
      (node (ref "R36") (pin "2") (pinfunction "2_2") (pintype "passive"))
    )
    (net (code "14") (name "/CH2_ACT") (class "Default")
      (node (ref "Q3") (pin "4") (pinfunction "C2_4") (pintype "passive"))
      (node (ref "Q3") (pin "5") (pinfunction "B1_5") (pintype "passive"))
      (node (ref "R9") (pin "2") (pinfunction "2_2") (pintype "passive"))
    )
    (net (code "15") (name "/CH2_ID") (class "Default")
      (node (ref "P1") (pin "5") (pinfunction "5_5") (pintype "passive"))
      (node (ref "R12") (pin "1") (pinfunction "1_1") (pintype "passive"))
      (node (ref "R37") (pin "1") (pinfunction "1_1") (pintype "passive"))
    )
    (net (code "16") (name "/CH2a_DRVn") (class "Default")
      (node (ref "D2a") (pin "1") (pinfunction "TP_1") (pintype "passive"))
      (node (ref "Q3") (pin "2") (pinfunction "B2_2") (pintype "passive"))
    )
    (net (code "17") (name "/CH2a_Htr+") (class "Default")
      (node (ref "C3") (pin "1") (pinfunction "1_1") (pintype "passive"))
      (node (ref "D1") (pin "K") (pinfunction "K_K") (pintype "passive"))
      (node (ref "H2a") (pin "1") (pinfunction "TP_1") (pintype "passive"))
      (node (ref "P1") (pin "4") (pinfunction "4_4") (pintype "passive"))
      (node (ref "Q1") (pin "5") (pinfunction "D2_5") (pintype "passive"))
      (node (ref "Q1") (pin "6") (pinfunction "D2_6") (pintype "passive"))
    )
    (net (code "18") (name "/CH2a_Thm+") (class "Default")
      (node (ref "P1") (pin "6") (pinfunction "6_6") (pintype "passive"))
      (node (ref "R31") (pin "1") (pinfunction "1_1") (pintype "passive"))
      (node (ref "R32") (pin "2") (pinfunction "2_2") (pintype "passive"))
    )
    (net (code "19") (name "/CH2b_DRVn") (class "Default")
      (node (ref "D2b") (pin "1") (pinfunction "TP_1") (pintype "passive"))
      (node (ref "Q4") (pin "2") (pinfunction "B2_2") (pintype "passive"))
    )
    (net (code "20") (name "/CH2b_Htr+") (class "Default")
      (node (ref "C4") (pin "1") (pinfunction "1_1") (pintype "passive"))
      (node (ref "D2") (pin "K") (pinfunction "K_K") (pintype "passive"))
      (node (ref "H2b") (pin "1") (pinfunction "TP_1") (pintype "passive"))
      (node (ref "P1") (pin "1") (pinfunction "1_1") (pintype "passive"))
      (node (ref "Q1") (pin "7") (pinfunction "D1_7") (pintype "passive"))
      (node (ref "Q1") (pin "8") (pinfunction "D1_8") (pintype "passive"))
    )
    (net (code "21") (name "/CH2b_Thm+") (class "Default")
      (node (ref "P1") (pin "3") (pinfunction "3_3") (pintype "passive"))
      (node (ref "R29") (pin "1") (pinfunction "1_1") (pintype "passive"))
      (node (ref "R34") (pin "2") (pinfunction "2_2") (pintype "passive"))
    )
    (net (code "22") (name "/COM") (class "Default")
      (node (ref "C14") (pin "1") (pinfunction "1_1") (pintype "passive"))
      (node (ref "C9") (pin "1") (pinfunction "1_1") (pintype "passive"))
      (node (ref "L2") (pin "2") (pinfunction "2_2") (pintype "passive"))
      (node (ref "NT1") (pin "2") (pinfunction "2_2") (pintype "passive"))
      (node (ref "P1") (pin "2") (pinfunction "2_2") (pintype "passive"))
      (node (ref "P2") (pin "2") (pinfunction "2_2") (pintype "passive"))
      (node (ref "Q12") (pin "2") (pinfunction "S_2") (pintype "passive"))
      (node (ref "R11") (pin "2") (pinfunction "2_2") (pintype "passive"))
      (node (ref "R17") (pin "2") (pinfunction "2_2") (pintype "passive"))
      (node (ref "R21") (pin "2") (pinfunction "2_2") (pintype "passive"))
      (node (ref "R24") (pin "1") (pinfunction "1_1") (pintype "passive"))
    )
    (net (code "23") (name "/Clamp") (class "Default")
      (node (ref "Q18") (pin "1") (pinfunction "G_1") (pintype "passive"))
    )
    (net (code "24") (name "/GAIN") (class "Default")
      (node (ref "R33") (pin "2") (pinfunction "2_2") (pintype "passive"))
    )
    (net (code "25") (name "/HIGH_G_AMP") (class "Default")
      (node (ref "D8") (pin "K") (pinfunction "K_K") (pintype "passive"))
      (node (ref "HGA") (pin "1") (pinfunction "TP_1") (pintype "passive"))
      (node (ref "R20") (pin "1") (pinfunction "1_1") (pintype "passive"))
    )
    (net (code "26") (name "/HIGH_G_IN") (class "Default")
      (node (ref "C16") (pin "2") (pinfunction "2_2") (pintype "passive"))
      (node (ref "R26") (pin "2") (pinfunction "2_2") (pintype "passive"))
      (node (ref "R27") (pin "2") (pinfunction "2_2") (pintype "passive"))
      (node (ref "U2") (pin "1") (pinfunction "A_1") (pintype "passive"))
      (node (ref "U2") (pin "5") (pinfunction "B+_5") (pintype "passive"))
    )
    (net (code "27") (name "/LOW_G_AMP") (class "Default")
      (node (ref "D10") (pin "K") (pinfunction "K_K") (pintype "passive"))
      (node (ref "LGA") (pin "1") (pinfunction "TP_1") (pintype "passive"))
      (node (ref "R27") (pin "1") (pinfunction "1_1") (pintype "passive"))
    )
    (net (code "28") (name "/LOW_G_IN") (class "Default")
      (node (ref "C37") (pin "2") (pinfunction "2_2") (pintype "passive"))
      (node (ref "Q18") (pin "3") (pinfunction "D_3") (pintype "passive"))
      (node (ref "R68") (pin "2") (pinfunction "2_2") (pintype "passive"))
      (node (ref "U2") (pin "3") (pinfunction "A+_3") (pintype "passive"))
      (node (ref "U3") (pin "13") (pinfunction "1Z_13") (pintype "passive"))
    )
    (net (code "29") (name "/MUX_SEL0{slash}ID1") (class "Default")
      (node (ref "R39") (pin "2") (pinfunction "2_2") (pintype "passive"))
      (node (ref "U3") (pin "9") (pinfunction "S1_9") (pintype "input"))
    )
    (net (code "30") (name "/MUX_SEL1{slash}ID2") (class "Default")
      (node (ref "R37") (pin "2") (pinfunction "2_2") (pintype "passive"))
      (node (ref "U3") (pin "10") (pinfunction "S0_10") (pintype "input"))
    )
    (net (code "31") (name "/OVERCURRENT") (class "Default")
      (node (ref "C10") (pin "2") (pinfunction "2_2") (pintype "passive"))
      (node (ref "OC") (pin "1") (pinfunction "TP_1") (pintype "passive"))
      (node (ref "R15") (pin "2") (pinfunction "2_2") (pintype "passive"))
      (node (ref "U1") (pin "4") (pinfunction "Out_4") (pintype "passive"))
    )
    (net (code "32") (name "EARTH") (class "Default")
      (node (ref "ER") (pin "1") (pinfunction "TP_1") (pintype "passive"))
      (node (ref "L2") (pin "1") (pinfunction "1_1") (pintype "passive"))
    )
    (net (code "33") (name "GND") (class "Default")
      (node (ref "C1") (pin "2") (pinfunction "2_2") (pintype "passive"))
      (node (ref "C11") (pin "2") (pinfunction "2_2") (pintype "passive"))
      (node (ref "C12") (pin "2") (pinfunction "2_2") (pintype "passive"))
      (node (ref "C13") (pin "2") (pinfunction "2_2") (pintype "passive"))
      (node (ref "C14") (pin "2") (pinfunction "2_2") (pintype "passive"))
      (node (ref "C17") (pin "1") (pinfunction "1_1") (pintype "passive"))
      (node (ref "C18") (pin "2") (pinfunction "2_2") (pintype "passive"))
      (node (ref "C19") (pin "2") (pinfunction "2_2") (pintype "passive"))
      (node (ref "C2") (pin "2") (pinfunction "2_2") (pintype "passive"))
      (node (ref "C3") (pin "2") (pinfunction "2_2") (pintype "passive"))
      (node (ref "C37") (pin "1") (pinfunction "1_1") (pintype "passive"))
      (node (ref "C4") (pin "2") (pinfunction "2_2") (pintype "passive"))
      (node (ref "C5") (pin "2") (pinfunction "2_2") (pintype "passive"))
      (node (ref "C6") (pin "2") (pinfunction "2_2") (pintype "passive"))
      (node (ref "C7") (pin "2") (pinfunction "2_2") (pintype "passive"))
      (node (ref "C8") (pin "2") (pinfunction "2_2") (pintype "passive"))
      (node (ref "D1") (pin "A") (pinfunction "A_A") (pintype "passive"))
      (node (ref "D10") (pin "A") (pinfunction "A_A") (pintype "passive"))
      (node (ref "D2") (pin "A") (pinfunction "A_A") (pintype "passive"))
      (node (ref "D3") (pin "A") (pinfunction "A_A") (pintype "passive"))
      (node (ref "D4") (pin "A") (pinfunction "A_A") (pintype "passive"))
      (node (ref "D5") (pin "K") (pinfunction "K_K") (pintype "passive"))
      (node (ref "D6") (pin "K") (pinfunction "K_K") (pintype "passive"))
      (node (ref "D8") (pin "A") (pinfunction "A_A") (pintype "passive"))
      (node (ref "NT1") (pin "1") (pinfunction "1_1") (pintype "passive"))
      (node (ref "Q18") (pin "2") (pinfunction "S_2") (pintype "passive"))
      (node (ref "Q7") (pin "2") (pinfunction "E_2") (pintype "passive"))
      (node (ref "R19") (pin "1") (pinfunction "1_1") (pintype "passive"))
      (node (ref "R68") (pin "1") (pinfunction "1_1") (pintype "passive"))
      (node (ref "U1") (pin "2") (pinfunction "V-_2") (pintype "power_in"))
      (node (ref "U3") (pin "1") (pinfunction "2Y0_1") (pintype "passive"))
      (node (ref "U3") (pin "2") (pinfunction "2Y2_2") (pintype "passive"))
      (node (ref "U3") (pin "3") (pinfunction "2Z_3") (pintype "passive"))
      (node (ref "U3") (pin "4") (pinfunction "2Y3_4") (pintype "passive"))
      (node (ref "U3") (pin "5") (pinfunction "2Y1_5") (pintype "passive"))
      (node (ref "U3") (pin "6") (pinfunction "En_6") (pintype "input"))
      (node (ref "U3") (pin "8") (pinfunction "Gnd_8") (pintype "power_in"))
    )
    (net (code "34") (name "Net-(C15-Pad2)") (class "Default")
      (node (ref "C15") (pin "2") (pinfunction "2_2") (pintype "passive"))
      (node (ref "R20") (pin "2") (pinfunction "2_2") (pintype "passive"))
      (node (ref "R23") (pin "2") (pinfunction "2_2") (pintype "passive"))
      (node (ref "U2") (pin "7") (pinfunction "7_7") (pintype "passive"))
    )
    (net (code "35") (name "Net-(D5-PadA)") (class "Default")
      (node (ref "D5") (pin "A") (pinfunction "A_A") (pintype "passive"))
      (node (ref "R9") (pin "1") (pinfunction "1_1") (pintype "passive"))
    )
    (net (code "36") (name "Net-(D6-PadA)") (class "Default")
      (node (ref "D6") (pin "A") (pinfunction "A_A") (pintype "passive"))
      (node (ref "R10") (pin "1") (pinfunction "1_1") (pintype "passive"))
    )
    (net (code "37") (name "Net-(Q1A-G1)") (class "Default")
      (node (ref "Q1") (pin "2") (pinfunction "G1_2") (pintype "passive"))
      (node (ref "R2") (pin "1") (pinfunction "1_1") (pintype "passive"))
      (node (ref "R6") (pin "2") (pinfunction "2_2") (pintype "passive"))
      (node (ref "Z2") (pin "A") (pinfunction "A_A") (pintype "passive"))
    )
    (net (code "38") (name "Net-(Q1B-G2)") (class "Default")
      (node (ref "Q1") (pin "4") (pinfunction "G2_4") (pintype "passive"))
      (node (ref "R1") (pin "1") (pinfunction "1_1") (pintype "passive"))
      (node (ref "R5") (pin "2") (pinfunction "2_2") (pintype "passive"))
      (node (ref "Z1") (pin "A") (pinfunction "A_A") (pintype "passive"))
    )
    (net (code "39") (name "Net-(Q2A-G1)") (class "Default")
      (node (ref "Q2") (pin "2") (pinfunction "G1_2") (pintype "passive"))
      (node (ref "R4") (pin "1") (pinfunction "1_1") (pintype "passive"))
      (node (ref "R8") (pin "2") (pinfunction "2_2") (pintype "passive"))
      (node (ref "Z4") (pin "A") (pinfunction "A_A") (pintype "passive"))
    )
    (net (code "40") (name "Net-(Q2B-G2)") (class "Default")
      (node (ref "Q2") (pin "4") (pinfunction "G2_4") (pintype "passive"))
      (node (ref "R3") (pin "1") (pinfunction "1_1") (pintype "passive"))
      (node (ref "R7") (pin "2") (pinfunction "2_2") (pintype "passive"))
      (node (ref "Z3") (pin "A") (pinfunction "A_A") (pintype "passive"))
    )
    (net (code "41") (name "Net-(Q3-C1)") (class "Default")
      (node (ref "Q3") (pin "1") (pinfunction "C1_1") (pintype "passive"))
      (node (ref "R5") (pin "1") (pinfunction "1_1") (pintype "passive"))
    )
    (net (code "42") (name "Net-(Q4-B1)") (class "Default")
      (node (ref "Q4") (pin "4") (pinfunction "C2_4") (pintype "passive"))
      (node (ref "Q4") (pin "5") (pinfunction "B1_5") (pintype "passive"))
    )
    (net (code "43") (name "Net-(Q4-C1)") (class "Default")
      (node (ref "Q4") (pin "1") (pinfunction "C1_1") (pintype "passive"))
      (node (ref "R6") (pin "1") (pinfunction "1_1") (pintype "passive"))
    )
    (net (code "44") (name "Net-(Q5-C1)") (class "Default")
      (node (ref "Q5") (pin "1") (pinfunction "C1_1") (pintype "passive"))
      (node (ref "R7") (pin "1") (pinfunction "1_1") (pintype "passive"))
    )
    (net (code "45") (name "Net-(Q6-B1)") (class "Default")
      (node (ref "Q6") (pin "4") (pinfunction "C2_4") (pintype "passive"))
      (node (ref "Q6") (pin "5") (pinfunction "B1_5") (pintype "passive"))
    )
    (net (code "46") (name "Net-(Q6-C1)") (class "Default")
      (node (ref "Q6") (pin "1") (pinfunction "C1_1") (pintype "passive"))
      (node (ref "R8") (pin "1") (pinfunction "1_1") (pintype "passive"))
    )
    (net (code "47") (name "Net-(Q7-B)") (class "Default")
      (node (ref "Q7") (pin "1") (pinfunction "B_1") (pintype "passive"))
      (node (ref "R18") (pin "1") (pinfunction "1_1") (pintype "passive"))
    )
    (net (code "48") (name "Net-(Q8-D)") (class "Default")
      (node (ref "Q8") (pin "3") (pinfunction "D_3") (pintype "passive"))
      (node (ref "R30") (pin "2") (pinfunction "2_2") (pintype "passive"))
    )
    (net (code "49") (name "Net-(Q9-D)") (class "Default")
      (node (ref "Q9") (pin "3") (pinfunction "D_3") (pintype "passive"))
      (node (ref "R28") (pin "2") (pinfunction "2_2") (pintype "passive"))
    )
    (net (code "50") (name "Net-(Q10-D)") (class "Default")
      (node (ref "Q10") (pin "3") (pinfunction "D_3") (pintype "passive"))
      (node (ref "R31") (pin "2") (pinfunction "2_2") (pintype "passive"))
    )
    (net (code "51") (name "Net-(Q10-G)") (class "Default")
      (node (ref "Q10") (pin "1") (pinfunction "G_1") (pintype "passive"))
      (node (ref "Q11") (pin "1") (pinfunction "G_1") (pintype "passive"))
      (node (ref "Q7") (pin "3") (pinfunction "C_3") (pintype "passive"))
      (node (ref "Q8") (pin "1") (pinfunction "G_1") (pintype "passive"))
      (node (ref "Q9") (pin "1") (pinfunction "G_1") (pintype "passive"))
      (node (ref "R16") (pin "2") (pinfunction "2_2") (pintype "passive"))
      (node (ref "R19") (pin "2") (pinfunction "2_2") (pintype "passive"))
    )
    (net (code "52") (name "Net-(Q10-S)") (class "Default")
      (node (ref "C17") (pin "2") (pinfunction "2_2") (pintype "passive"))
      (node (ref "Q10") (pin "2") (pinfunction "S_2") (pintype "passive"))
      (node (ref "Q11") (pin "2") (pinfunction "S_2") (pintype "passive"))
      (node (ref "Q8") (pin "2") (pinfunction "S_2") (pintype "passive"))
      (node (ref "Q9") (pin "2") (pinfunction "S_2") (pintype "passive"))
      (node (ref "R22") (pin "2") (pinfunction "2_2") (pintype "passive"))
    )
    (net (code "53") (name "Net-(Q11-D)") (class "Default")
      (node (ref "Q11") (pin "3") (pinfunction "D_3") (pintype "passive"))
      (node (ref "R29") (pin "2") (pinfunction "2_2") (pintype "passive"))
    )
    (net (code "54") (name "Net-(Q12-D)") (class "Default")
      (node (ref "Q12") (pin "3") (pinfunction "D_3") (pintype "passive"))
      (node (ref "R25") (pin "2") (pinfunction "2_2") (pintype "passive"))
    )
    (net (code "55") (name "Net-(Q12-G)") (class "Default")
      (node (ref "Q12") (pin "1") (pinfunction "G_1") (pintype "passive"))
      (node (ref "Q13") (pin "3") (pinfunction "C_3") (pintype "passive"))
      (node (ref "R38") (pin "2") (pinfunction "2_2") (pintype "passive"))
    )
    (net (code "56") (name "Net-(Q13-B)") (class "Default")
      (node (ref "Q13") (pin "1") (pinfunction "B_1") (pintype "passive"))
      (node (ref "R33") (pin "1") (pinfunction "1_1") (pintype "passive"))
    )
    (net (code "57") (name "Net-(U1A-In+)") (class "Default")
      (node (ref "R11") (pin "1") (pinfunction "1_1") (pintype "passive"))
      (node (ref "U1") (pin "1") (pinfunction "In+_1") (pintype "passive"))
    )
    (net (code "58") (name "Net-(U1A-In-)") (class "Default")
      (node (ref "C10") (pin "1") (pinfunction "1_1") (pintype "passive"))
      (node (ref "R14") (pin "1") (pinfunction "1_1") (pintype "passive"))
      (node (ref "R15") (pin "1") (pinfunction "1_1") (pintype "passive"))
      (node (ref "U1") (pin "3") (pinfunction "In-_3") (pintype "passive"))
    )
    (net (code "59") (name "Net-(U2A-A-)") (class "Default")
      (node (ref "C16") (pin "1") (pinfunction "1_1") (pintype "passive"))
      (node (ref "R24") (pin "2") (pinfunction "2_2") (pintype "passive"))
      (node (ref "R25") (pin "1") (pinfunction "1_1") (pintype "passive"))
      (node (ref "R26") (pin "1") (pinfunction "1_1") (pintype "passive"))
      (node (ref "U2") (pin "2") (pinfunction "A-_2") (pintype "passive"))
    )
    (net (code "60") (name "Net-(U2B-B-)") (class "Default")
      (node (ref "C15") (pin "1") (pinfunction "1_1") (pintype "passive"))
      (node (ref "R21") (pin "1") (pinfunction "1_1") (pintype "passive"))
      (node (ref "R23") (pin "1") (pinfunction "1_1") (pintype "passive"))
      (node (ref "U2") (pin "6") (pinfunction "B-_6") (pintype "passive"))
    )
    (net (code "61") (name "Net-(U3-1Y0)") (class "Default")
      (node (ref "R32") (pin "1") (pinfunction "1_1") (pintype "passive"))
      (node (ref "U3") (pin "12") (pinfunction "1Y0_12") (pintype "passive"))
    )
    (net (code "62") (name "Net-(U3-1Y1)") (class "Default")
      (node (ref "R35") (pin "1") (pinfunction "1_1") (pintype "passive"))
      (node (ref "U3") (pin "14") (pinfunction "1Y1_14") (pintype "passive"))
    )
    (net (code "63") (name "Net-(U3-1Y2)") (class "Default")
      (node (ref "R34") (pin "1") (pinfunction "1_1") (pintype "passive"))
      (node (ref "U3") (pin "15") (pinfunction "1Y2_15") (pintype "passive"))
    )
    (net (code "64") (name "Net-(U3-1Y3)") (class "Default")
      (node (ref "R36") (pin "1") (pinfunction "1_1") (pintype "passive"))
      (node (ref "U3") (pin "11") (pinfunction "1Y3_11") (pintype "passive"))
    )
    (net (code "65") (name "Vnn") (class "Default")
      (node (ref "C9") (pin "2") (pinfunction "2_2") (pintype "passive"))
      (node (ref "R14") (pin "2") (pinfunction "2_2") (pintype "passive"))
      (node (ref "R17") (pin "1") (pinfunction "1_1") (pintype "passive"))
    )
    (net (code "66") (name "Vpp") (class "Default")
      (node (ref "Q1") (pin "1") (pinfunction "S1_1") (pintype "passive"))
      (node (ref "Q1") (pin "3") (pinfunction "S2_3") (pintype "passive"))
      (node (ref "Q2") (pin "1") (pinfunction "S1_1") (pintype "passive"))
      (node (ref "Q2") (pin "3") (pinfunction "S2_3") (pintype "passive"))
      (node (ref "R1") (pin "2") (pinfunction "2_2") (pintype "passive"))
      (node (ref "R2") (pin "2") (pinfunction "2_2") (pintype "passive"))
      (node (ref "R3") (pin "2") (pinfunction "2_2") (pintype "passive"))
      (node (ref "R4") (pin "2") (pinfunction "2_2") (pintype "passive"))
      (node (ref "Z1") (pin "K") (pinfunction "K_K") (pintype "passive"))
      (node (ref "Z2") (pin "K") (pinfunction "K_K") (pintype "passive"))
      (node (ref "Z3") (pin "K") (pinfunction "K_K") (pintype "passive"))
      (node (ref "Z4") (pin "K") (pinfunction "K_K") (pintype "passive"))
    )
  )
)
